# hamilton.net
KiCad netlist of a schematic drawn in EAGLE
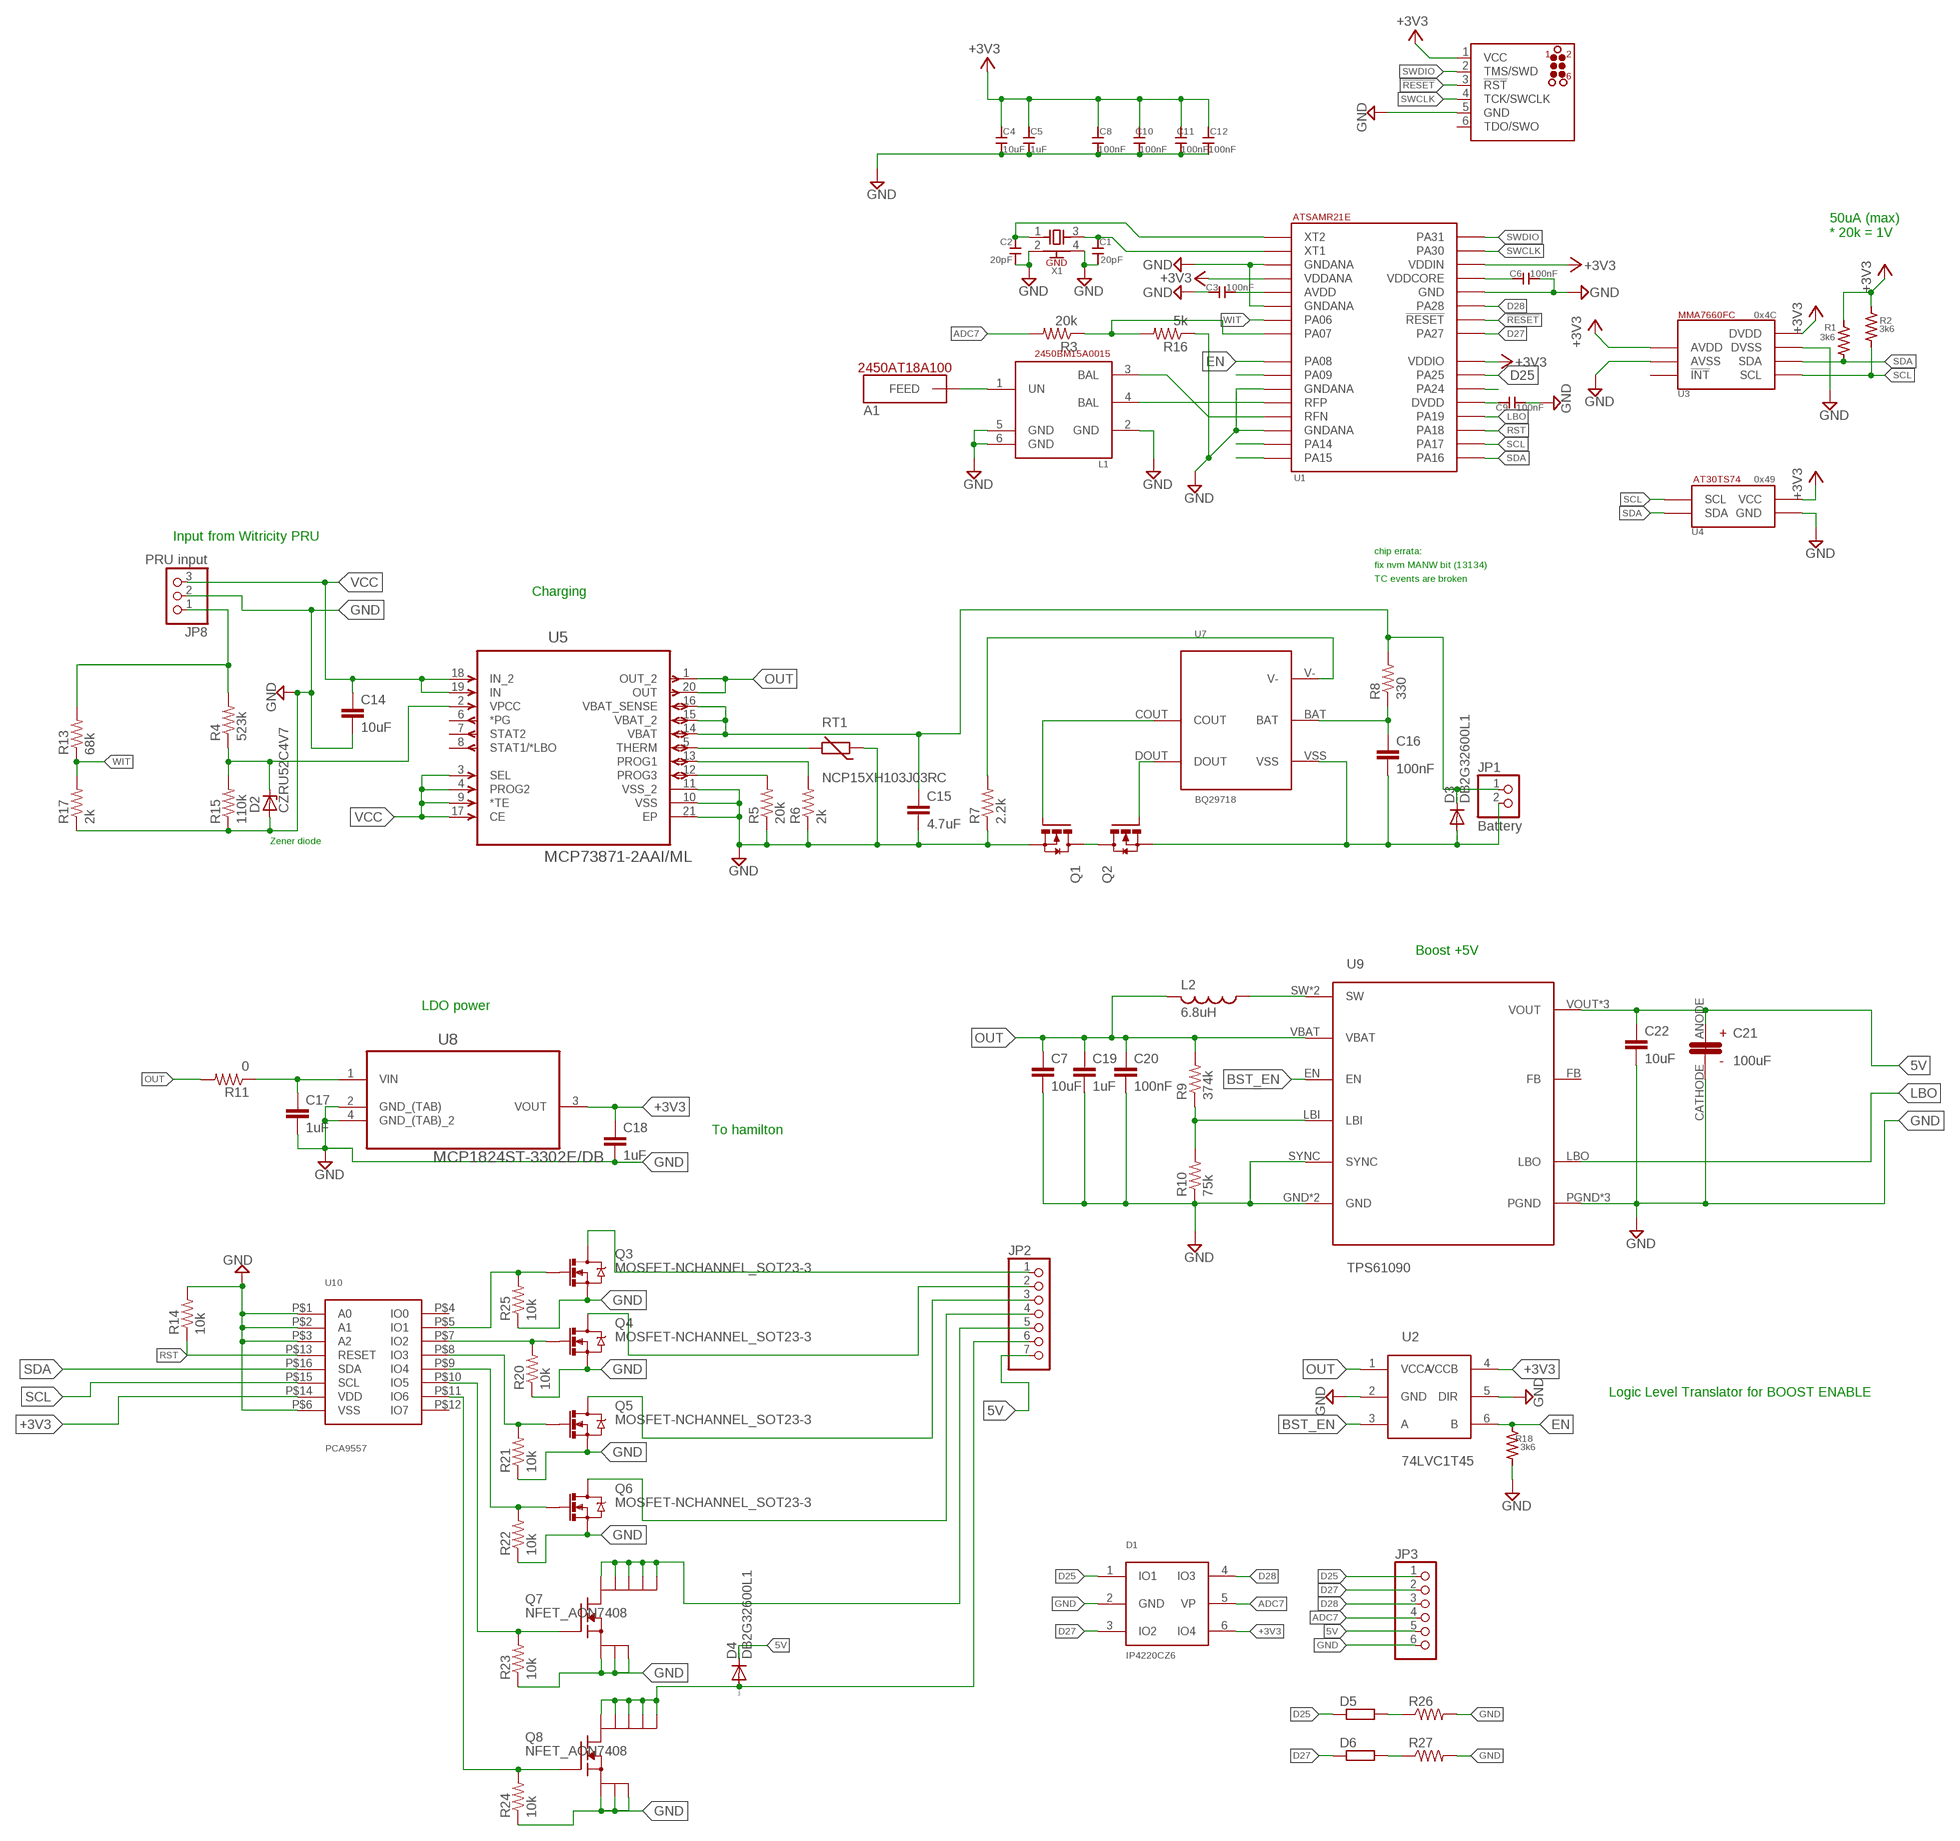
[diagram p0: schematic, sheet 1]

(export (version "E")
  (design (tool "Eeschema 10.0.6"))
  (components
    (comp (ref "A1")
      (value "JOHANSON_ANTENNA2")
      (footprint "eagle-import:JOHANSON_ANTENNA2")
      (libsource (lib "eagle-import") (part "JOHANSON_ANTENNA2"))
    )
    (comp (ref "C1")
      (value "20pF")
      (footprint "eagle-import:S0402")
      (libsource (lib "eagle-import") (part "0603_CAPACITORSMALL"))
    )
    (comp (ref "C2")
      (value "20pF")
      (footprint "eagle-import:S0402")
      (libsource (lib "eagle-import") (part "0603_CAPACITORSMALL"))
    )
    (comp (ref "C3")
      (value "100nF")
      (footprint "eagle-import:C0402")
      (libsource (lib "eagle-import") (part "0603_CAPACITOR0402"))
    )
    (comp (ref "C4")
      (value "10uF")
      (footprint "eagle-import:0805")
      (libsource (lib "eagle-import") (part "0805_CAPACITOR"))
    )
    (comp (ref "C5")
      (value "1uF")
      (footprint "eagle-import:C0402")
      (libsource (lib "eagle-import") (part "0603_CAPACITOR0402"))
    )
    (comp (ref "C6")
      (value "100nF")
      (footprint "eagle-import:C0402")
      (libsource (lib "eagle-import") (part "0603_CAPACITOR0402"))
    )
    (comp (ref "C7")
      (value "10uF")
      (footprint "eagle-import:C0603")
      (libsource (lib "eagle-import") (part "C-EUC0603"))
    )
    (comp (ref "C8")
      (value "100nF")
      (footprint "eagle-import:C0402")
      (libsource (lib "eagle-import") (part "0603_CAPACITOR0402"))
    )
    (comp (ref "C9")
      (value "100nF")
      (footprint "eagle-import:C0402")
      (libsource (lib "eagle-import") (part "0603_CAPACITOR0402"))
    )
    (comp (ref "C10")
      (value "100nF")
      (footprint "eagle-import:C0402")
      (libsource (lib "eagle-import") (part "0603_CAPACITOR0402"))
    )
    (comp (ref "C11")
      (value "100nF")
      (footprint "eagle-import:C0402")
      (libsource (lib "eagle-import") (part "0603_CAPACITOR0402"))
    )
    (comp (ref "C12")
      (value "100nF")
      (footprint "eagle-import:C0402")
      (libsource (lib "eagle-import") (part "0603_CAPACITOR0402"))
    )
    (comp (ref "C14")
      (value "10uF")
      (footprint "eagle-import:C0603")
      (libsource (lib "eagle-import") (part "C-EUC0603"))
    )
    (comp (ref "C15")
      (value "4.7uF")
      (footprint "eagle-import:C0603")
      (libsource (lib "eagle-import") (part "C-EUC0603"))
    )
    (comp (ref "C16")
      (value "100nF")
      (footprint "eagle-import:C0603")
      (libsource (lib "eagle-import") (part "C-EUC0603"))
    )
    (comp (ref "C17")
      (value "1uF")
      (footprint "eagle-import:C0603")
      (libsource (lib "eagle-import") (part "C-EUC0603"))
    )
    (comp (ref "C18")
      (value "1uF")
      (footprint "eagle-import:C0603")
      (libsource (lib "eagle-import") (part "C-EUC0603"))
    )
    (comp (ref "C19")
      (value "1uF")
      (footprint "eagle-import:C0603")
      (libsource (lib "eagle-import") (part "C-EUC0603"))
    )
    (comp (ref "C20")
      (value "100nF")
      (footprint "eagle-import:C0603")
      (libsource (lib "eagle-import") (part "C-EUC0603"))
    )
    (comp (ref "C21")
      (value "100uF")
      (footprint "eagle-import:6032")
      (libsource (lib "eagle-import") (part "T491C686K010AT"))
    )
    (comp (ref "C22")
      (value "10uF")
      (footprint "eagle-import:C0603")
      (libsource (lib "eagle-import") (part "C-EUC0603"))
    )
    (comp (ref "D1")
      (value "IP4220CZ6")
      (footprint "eagle-import:SOT457")
      (libsource (lib "eagle-import") (part "IP4220CZ6"))
    )
    (comp (ref "D2")
      (value "CZRU52C4V7")
      (footprint "eagle-import:R0603")
      (libsource (lib "eagle-import") (part "CZRU52C4V7"))
    )
    (comp (ref "D3")
      (value "DB2G32600L1")
      (footprint "eagle-import:R0402")
      (libsource (lib "eagle-import") (part "DB2G32600L1"))
    )
    (comp (ref "D4")
      (value "DB2G32600L1")
      (footprint "eagle-import:R0402")
      (libsource (lib "eagle-import") (part "DB2G32600L1"))
    )
    (comp (ref "D5")
      (value "R-EU_R0603")
      (footprint "eagle-import:R0603")
      (libsource (lib "eagle-import") (part "R-EU_R0603"))
    )
    (comp (ref "D6")
      (value "R-EU_R0603")
      (footprint "eagle-import:R0603")
      (libsource (lib "eagle-import") (part "R-EU_R0603"))
    )
    (comp (ref "JP1")
      (value "Battery")
      (footprint "eagle-import:1X02")
      (libsource (lib "eagle-import") (part "PINHD-1X2"))
    )
    (comp (ref "JP2")
      (value "PINHD-1X7")
      (footprint "eagle-import:1X07")
      (libsource (lib "eagle-import") (part "PINHD-1X7"))
    )
    (comp (ref "JP3")
      (value "PINHD-1X6")
      (footprint "eagle-import:1X06")
      (libsource (lib "eagle-import") (part "PINHD-1X6"))
    )
    (comp (ref "JP8")
      (value "PRU input")
      (footprint "eagle-import:1X03")
      (libsource (lib "eagle-import") (part "PINHD-1X3"))
    )
    (comp (ref "L1")
      (value "BALUN_JOHANSON")
      (footprint "eagle-import:BALUN_JOHANSON")
      (libsource (lib "eagle-import") (part "BALUN_JOHANSON"))
    )
    (comp (ref "L2")
      (value "6.8uH")
      (footprint "eagle-import:2-SMD-7.8-7-5")
      (libsource (lib "eagle-import") (part "L-744787068"))
    )
    (comp (ref "Q1")
      (value "CSD16301Q2")
      (footprint "eagle-import:6-SMD")
      (libsource (lib "eagle-import") (part "CSD16301Q2"))
    )
    (comp (ref "Q2")
      (value "CSD16301Q2")
      (footprint "eagle-import:6-SMD")
      (libsource (lib "eagle-import") (part "CSD16301Q2"))
    )
    (comp (ref "Q3")
      (value "MOSFET-NCHANNEL_SOT23-3")
      (footprint "eagle-import:SOT23-3")
      (libsource (lib "eagle-import") (part "MOSFET-NCHANNEL_SOT23-3"))
    )
    (comp (ref "Q4")
      (value "MOSFET-NCHANNEL_SOT23-3")
      (footprint "eagle-import:SOT23-3")
      (libsource (lib "eagle-import") (part "MOSFET-NCHANNEL_SOT23-3"))
    )
    (comp (ref "Q5")
      (value "MOSFET-NCHANNEL_SOT23-3")
      (footprint "eagle-import:SOT23-3")
      (libsource (lib "eagle-import") (part "MOSFET-NCHANNEL_SOT23-3"))
    )
    (comp (ref "Q6")
      (value "MOSFET-NCHANNEL_SOT23-3")
      (footprint "eagle-import:SOT23-3")
      (libsource (lib "eagle-import") (part "MOSFET-NCHANNEL_SOT23-3"))
    )
    (comp (ref "Q7")
      (value "NFET_AON7408")
      (footprint "eagle-import:VDFN3X38L")
      (libsource (lib "eagle-import") (part "NFET_AON7408"))
    )
    (comp (ref "Q8")
      (value "NFET_AON7408")
      (footprint "eagle-import:VDFN3X38L")
      (libsource (lib "eagle-import") (part "NFET_AON7408"))
    )
    (comp (ref "R1")
      (value "3k6")
      (footprint "eagle-import:S0402")
      (libsource (lib "eagle-import") (part "0603_RESISTORSMALL"))
    )
    (comp (ref "R2")
      (value "3k6")
      (footprint "eagle-import:S0402")
      (libsource (lib "eagle-import") (part "0603_RESISTORSMALL"))
    )
    (comp (ref "R3")
      (value "20k")
      (footprint "eagle-import:R0402")
      (libsource (lib "eagle-import") (part "R-US_R0402"))
    )
    (comp (ref "R4")
      (value "523k")
      (footprint "eagle-import:R0603")
      (libsource (lib "eagle-import") (part "R-US_R0603"))
    )
    (comp (ref "R5")
      (value "20k")
      (footprint "eagle-import:R0603")
      (libsource (lib "eagle-import") (part "R-US_R0603"))
    )
    (comp (ref "R6")
      (value "2k")
      (footprint "eagle-import:R0603")
      (libsource (lib "eagle-import") (part "R-US_R0603"))
    )
    (comp (ref "R7")
      (value "2.2k")
      (footprint "eagle-import:R0603")
      (libsource (lib "eagle-import") (part "R-US_R0603"))
    )
    (comp (ref "R8")
      (value "330")
      (footprint "eagle-import:R0603")
      (libsource (lib "eagle-import") (part "R-US_R0603"))
    )
    (comp (ref "R9")
      (value "374k")
      (footprint "eagle-import:R0603")
      (libsource (lib "eagle-import") (part "R-US_R0603"))
    )
    (comp (ref "R10")
      (value "75k")
      (footprint "eagle-import:R0603")
      (libsource (lib "eagle-import") (part "R-US_R0603"))
    )
    (comp (ref "R11")
      (value "0")
      (footprint "eagle-import:R0603")
      (libsource (lib "eagle-import") (part "R-US_R0603"))
    )
    (comp (ref "R13")
      (value "68k")
      (footprint "eagle-import:R0402")
      (libsource (lib "eagle-import") (part "R-US_R0402"))
    )
    (comp (ref "R14")
      (value "10k")
      (footprint "eagle-import:R0603")
      (libsource (lib "eagle-import") (part "R-US_R0603"))
    )
    (comp (ref "R15")
      (value "110k")
      (footprint "eagle-import:R0603")
      (libsource (lib "eagle-import") (part "R-US_R0603"))
    )
    (comp (ref "R16")
      (value "5k")
      (footprint "eagle-import:R0402")
      (libsource (lib "eagle-import") (part "R-US_R0402"))
    )
    (comp (ref "R17")
      (value "2k")
      (footprint "eagle-import:R0402")
      (libsource (lib "eagle-import") (part "R-US_R0402"))
    )
    (comp (ref "R18")
      (value "3k6")
      (footprint "eagle-import:S0402")
      (libsource (lib "eagle-import") (part "0603_RESISTORSMALL"))
    )
    (comp (ref "R20")
      (value "10k")
      (footprint "eagle-import:R0402")
      (libsource (lib "eagle-import") (part "R-US_R0402"))
    )
    (comp (ref "R21")
      (value "10k")
      (footprint "eagle-import:R0402")
      (libsource (lib "eagle-import") (part "R-US_R0402"))
    )
    (comp (ref "R22")
      (value "10k")
      (footprint "eagle-import:R0402")
      (libsource (lib "eagle-import") (part "R-US_R0402"))
    )
    (comp (ref "R23")
      (value "10k")
      (footprint "eagle-import:R0402")
      (libsource (lib "eagle-import") (part "R-US_R0402"))
    )
    (comp (ref "R24")
      (value "10k")
      (footprint "eagle-import:R0402")
      (libsource (lib "eagle-import") (part "R-US_R0402"))
    )
    (comp (ref "R25")
      (value "10k")
      (footprint "eagle-import:R0402")
      (libsource (lib "eagle-import") (part "R-US_R0402"))
    )
    (comp (ref "R26")
      (value "R-US_R0402")
      (footprint "eagle-import:R0402")
      (libsource (lib "eagle-import") (part "R-US_R0402"))
    )
    (comp (ref "R27")
      (value "R-US_R0402")
      (footprint "eagle-import:R0402")
      (libsource (lib "eagle-import") (part "R-US_R0402"))
    )
    (comp (ref "RT1")
      (value "NCP15XH103J03RC")
      (footprint "eagle-import:CT_CN0402")
      (libsource (lib "eagle-import") (part "NCP15XH103J03RC"))
    )
    (comp (ref "U$1")
      (value "JLINK_CONNECT")
      (footprint "eagle-import:TC2030-MCP-NL")
      (libsource (lib "eagle-import") (part "JLINK_CONNECT"))
    )
    (comp (ref "U1")
      (value "SAMR21")
      (footprint "eagle-import:QFN32")
      (libsource (lib "eagle-import") (part "SAMR21"))
    )
    (comp (ref "U2")
      (value "74LVC1T45")
      (footprint "eagle-import:SOT891")
      (libsource (lib "eagle-import") (part "74LVC1T45"))
    )
    (comp (ref "U3")
      (value "MMA7660FC")
      (footprint "eagle-import:MMA7660")
      (libsource (lib "eagle-import") (part "MMA7660FC"))
    )
    (comp (ref "U4")
      (value "AT30TS74")
      (footprint "eagle-import:4WLCSP")
      (libsource (lib "eagle-import") (part "AT30TS74"))
    )
    (comp (ref "U5")
      (value "MCP73871-2AAI/ML")
      (footprint "eagle-import:QFN50P400X400X100-21N")
      (libsource (lib "eagle-import") (part "MCP73871-2AAI/ML"))
    )
    (comp (ref "U7")
      (value "BQ29718")
      (footprint "eagle-import:6-WFDFN")
      (libsource (lib "eagle-import") (part "BQ29718"))
    )
    (comp (ref "U8")
      (value "MCP1824ST-3302E/DB")
      (footprint "eagle-import:SOT230P700X180-4N")
      (libsource (lib "eagle-import") (part "MCP1824ST-3302E/DB"))
    )
    (comp (ref "U9")
      (value "TPS61090")
      (footprint "eagle-import:QFN-16")
      (libsource (lib "eagle-import") (part "TPS61090"))
    )
    (comp (ref "U10")
      (value "PCA9557")
      (footprint "eagle-import:SOT629-1")
      (libsource (lib "eagle-import") (part "PCA9557"))
    )
    (comp (ref "X1")
      (value "XTAL")
      (footprint "eagle-import:XTAL")
      (libsource (lib "eagle-import") (part "XTAL"))
    )
  )
  (nets
    (net (code "1") (name "+3V3") (class "Default")
      (node (ref "C10") (pin "1") (pinfunction "P$1_1") (pintype "passive"))
      (node (ref "C11") (pin "1") (pinfunction "P$1_1") (pintype "passive"))
      (node (ref "C12") (pin "1") (pinfunction "P$1_1") (pintype "passive"))
      (node (ref "C18") (pin "1") (pinfunction "1_1") (pintype "passive"))
      (node (ref "C4") (pin "2") (pinfunction "P$2_2") (pintype "passive"))
      (node (ref "C5") (pin "2") (pinfunction "P$2_2") (pintype "passive"))
      (node (ref "C8") (pin "1") (pinfunction "P$1_1") (pintype "passive"))
      (node (ref "D1") (pin "6") (pinfunction "IO4_6") (pintype "bidirectional"))
      (node (ref "R1") (pin "P$2") (pinfunction "P$2_P$2") (pintype "passive"))
      (node (ref "R2") (pin "P$2") (pinfunction "P$2_P$2") (pintype "passive"))
      (node (ref "U$1") (pin "1") (pinfunction "VCC_1") (pintype "passive"))
      (node (ref "U1") (pin "24") (pinfunction "VDDIO_24") (pintype "bidirectional"))
      (node (ref "U1") (pin "30") (pinfunction "VDDIN_30") (pintype "bidirectional"))
      (node (ref "U1") (pin "4") (pinfunction "VDDANA_4") (pintype "bidirectional"))
      (node (ref "U10") (pin "P$14") (pinfunction "VDD_P$14") (pintype "bidirectional"))
      (node (ref "U2") (pin "4") (pinfunction "VCCB_4") (pintype "bidirectional"))
      (node (ref "U3") (pin "3") (pinfunction "AVDD_3") (pintype "bidirectional"))
      (node (ref "U3") (pin "9") (pinfunction "DVDD_9") (pintype "bidirectional"))
      (node (ref "U4") (pin "A1") (pinfunction "VCC_A1") (pintype "bidirectional"))
      (node (ref "U8") (pin "3") (pinfunction "VOUT_3") (pintype "output"))
    )
    (net (code "2") (name "/~{RESET}") (class "Default")
      (node (ref "U$1") (pin "3") (pinfunction "~{RST}_3") (pintype "bidirectional"))
      (node (ref "U1") (pin "26") (pinfunction "~{RESET}_26") (pintype "bidirectional"))
    )
    (net (code "3") (name "5V") (class "Default")
      (node (ref "C21") (pin "ANODE") (pinfunction "ANODE_ANODE") (pintype "bidirectional"))
      (node (ref "C22") (pin "1") (pinfunction "1_1") (pintype "passive"))
      (node (ref "D4") (pin "C") (pinfunction "C_C") (pintype "passive"))
      (node (ref "JP2") (pin "7") (pinfunction "7_7") (pintype "passive"))
      (node (ref "JP3") (pin "5") (pinfunction "5_5") (pintype "passive"))
      (node (ref "U9") (pin "VOUT") (pinfunction "VOUT_VOUT") (pintype "bidirectional"))
      (node (ref "U9") (pin "VOUT_2") (pinfunction "VOUT_VOUT_2") (pintype "bidirectional"))
      (node (ref "U9") (pin "VOUT_3") (pinfunction "VOUT_VOUT_3") (pintype "bidirectional"))
    )
    (net (code "4") (name "ADC7") (class "Default")
      (node (ref "D1") (pin "5") (pinfunction "VP_5") (pintype "bidirectional"))
      (node (ref "JP3") (pin "4") (pinfunction "4_4") (pintype "passive"))
      (node (ref "R3") (pin "2") (pinfunction "2_2") (pintype "passive"))
    )
    (net (code "5") (name "BST_EN") (class "Default")
      (node (ref "U2") (pin "3") (pinfunction "A_3") (pintype "bidirectional"))
      (node (ref "U9") (pin "EN") (pinfunction "EN_EN") (pintype "bidirectional"))
    )
    (net (code "6") (name "D25") (class "Default")
      (node (ref "D1") (pin "1") (pinfunction "IO1_1") (pintype "bidirectional"))
      (node (ref "D5") (pin "1") (pinfunction "1_1") (pintype "passive"))
      (node (ref "JP3") (pin "1") (pinfunction "1_1") (pintype "passive"))
      (node (ref "U1") (pin "23") (pinfunction "PA25_23") (pintype "bidirectional"))
    )
    (net (code "7") (name "D27") (class "Default")
      (node (ref "D1") (pin "3") (pinfunction "IO2_3") (pintype "bidirectional"))
      (node (ref "D6") (pin "1") (pinfunction "1_1") (pintype "passive"))
      (node (ref "JP3") (pin "2") (pinfunction "2_2") (pintype "passive"))
      (node (ref "U1") (pin "25") (pinfunction "PA27_25") (pintype "bidirectional"))
    )
    (net (code "8") (name "D28") (class "Default")
      (node (ref "D1") (pin "4") (pinfunction "IO3_4") (pintype "bidirectional"))
      (node (ref "JP3") (pin "3") (pinfunction "3_3") (pintype "passive"))
      (node (ref "U1") (pin "27") (pinfunction "PA28_27") (pintype "bidirectional"))
    )
    (net (code "9") (name "EN") (class "Default")
      (node (ref "R18") (pin "P$2") (pinfunction "P$2_P$2") (pintype "passive"))
      (node (ref "U1") (pin "9") (pinfunction "PA08_9") (pintype "bidirectional"))
      (node (ref "U2") (pin "6") (pinfunction "B_6") (pintype "bidirectional"))
    )
    (net (code "10") (name "GND") (class "Default")
      (node (ref "C1") (pin "P$1") (pinfunction "P$1_P$1") (pintype "passive"))
      (node (ref "C10") (pin "2") (pinfunction "P$2_2") (pintype "passive"))
      (node (ref "C11") (pin "2") (pinfunction "P$2_2") (pintype "passive"))
      (node (ref "C12") (pin "2") (pinfunction "P$2_2") (pintype "passive"))
      (node (ref "C14") (pin "2") (pinfunction "2_2") (pintype "passive"))
      (node (ref "C15") (pin "2") (pinfunction "2_2") (pintype "passive"))
      (node (ref "C17") (pin "2") (pinfunction "2_2") (pintype "passive"))
      (node (ref "C18") (pin "2") (pinfunction "2_2") (pintype "passive"))
      (node (ref "C19") (pin "2") (pinfunction "2_2") (pintype "passive"))
      (node (ref "C2") (pin "P$1") (pinfunction "P$1_P$1") (pintype "passive"))
      (node (ref "C20") (pin "2") (pinfunction "2_2") (pintype "passive"))
      (node (ref "C21") (pin "CATHODE") (pinfunction "CATHODE_CATHODE") (pintype "bidirectional"))
      (node (ref "C22") (pin "2") (pinfunction "2_2") (pintype "passive"))
      (node (ref "C3") (pin "2") (pinfunction "P$2_2") (pintype "passive"))
      (node (ref "C4") (pin "1") (pinfunction "P$1_1") (pintype "passive"))
      (node (ref "C5") (pin "1") (pinfunction "P$1_1") (pintype "passive"))
      (node (ref "C6") (pin "1") (pinfunction "P$1_1") (pintype "passive"))
      (node (ref "C7") (pin "2") (pinfunction "2_2") (pintype "passive"))
      (node (ref "C8") (pin "2") (pinfunction "P$2_2") (pintype "passive"))
      (node (ref "C9") (pin "1") (pinfunction "P$1_1") (pintype "passive"))
      (node (ref "D1") (pin "2") (pinfunction "GND_2") (pintype "bidirectional"))
      (node (ref "D2") (pin "A") (pinfunction "A_A") (pintype "passive"))
      (node (ref "JP3") (pin "6") (pinfunction "6_6") (pintype "passive"))
      (node (ref "JP8") (pin "2") (pinfunction "2_2") (pintype "passive"))
      (node (ref "L1") (pin "2") (pinfunction "GND_2") (pintype "bidirectional"))
      (node (ref "L1") (pin "5") (pinfunction "GND_5") (pintype "bidirectional"))
      (node (ref "L1") (pin "6") (pinfunction "GND_6") (pintype "bidirectional"))
      (node (ref "Q1") (pin "S_1") (pinfunction "S_S_1") (pintype "passive"))
      (node (ref "Q1") (pin "S_2") (pinfunction "S_S_2") (pintype "passive"))
      (node (ref "Q3") (pin "2") (pinfunction "S_2") (pintype "passive"))
      (node (ref "Q4") (pin "2") (pinfunction "S_2") (pintype "passive"))
      (node (ref "Q5") (pin "2") (pinfunction "S_2") (pintype "passive"))
      (node (ref "Q6") (pin "2") (pinfunction "S_2") (pintype "passive"))
      (node (ref "Q7") (pin "1") (pinfunction "S_1") (pintype "passive"))
      (node (ref "Q7") (pin "2") (pinfunction "S_2") (pintype "bidirectional"))
      (node (ref "Q7") (pin "3") (pinfunction "S_3") (pintype "bidirectional"))
      (node (ref "Q8") (pin "1") (pinfunction "S_1") (pintype "passive"))
      (node (ref "Q8") (pin "2") (pinfunction "S_2") (pintype "bidirectional"))
      (node (ref "Q8") (pin "3") (pinfunction "S_3") (pintype "bidirectional"))
      (node (ref "R10") (pin "1") (pinfunction "1_1") (pintype "passive"))
      (node (ref "R14") (pin "2") (pinfunction "2_2") (pintype "passive"))
      (node (ref "R15") (pin "1") (pinfunction "1_1") (pintype "passive"))
      (node (ref "R16") (pin "1") (pinfunction "1_1") (pintype "passive"))
      (node (ref "R17") (pin "1") (pinfunction "1_1") (pintype "passive"))
      (node (ref "R18") (pin "P$1") (pinfunction "P$1_P$1") (pintype "passive"))
      (node (ref "R20") (pin "1") (pinfunction "1_1") (pintype "passive"))
      (node (ref "R21") (pin "1") (pinfunction "1_1") (pintype "passive"))
      (node (ref "R22") (pin "1") (pinfunction "1_1") (pintype "passive"))
      (node (ref "R23") (pin "1") (pinfunction "1_1") (pintype "passive"))
      (node (ref "R24") (pin "1") (pinfunction "1_1") (pintype "passive"))
      (node (ref "R25") (pin "1") (pinfunction "1_1") (pintype "passive"))
      (node (ref "R26") (pin "2") (pinfunction "2_2") (pintype "passive"))
      (node (ref "R27") (pin "2") (pinfunction "2_2") (pintype "passive"))
      (node (ref "R5") (pin "1") (pinfunction "1_1") (pintype "passive"))
      (node (ref "R6") (pin "1") (pinfunction "1_1") (pintype "passive"))
      (node (ref "R7") (pin "1") (pinfunction "1_1") (pintype "passive"))
      (node (ref "RT1") (pin "1") (pinfunction "1_1") (pintype "passive"))
      (node (ref "U$1") (pin "5") (pinfunction "GND_5") (pintype "power_in"))
      (node (ref "U1") (pin "11") (pinfunction "GNDANA_11") (pintype "bidirectional"))
      (node (ref "U1") (pin "14") (pinfunction "GNDANA_14") (pintype "bidirectional"))
      (node (ref "U1") (pin "28") (pinfunction "GND_28") (pintype "bidirectional"))
      (node (ref "U1") (pin "3") (pinfunction "GNDANA_3") (pintype "bidirectional"))
      (node (ref "U1") (pin "6") (pinfunction "GNDANA_6") (pintype "bidirectional"))
      (node (ref "U10") (pin "P$1") (pinfunction "A0_P$1") (pintype "bidirectional"))
      (node (ref "U10") (pin "P$2") (pinfunction "A1_P$2") (pintype "bidirectional"))
      (node (ref "U10") (pin "P$3") (pinfunction "A2_P$3") (pintype "bidirectional"))
      (node (ref "U10") (pin "P$6") (pinfunction "VSS_P$6") (pintype "bidirectional"))
      (node (ref "U2") (pin "2") (pinfunction "GND_2") (pintype "bidirectional"))
      (node (ref "U2") (pin "5") (pinfunction "DIR_5") (pintype "bidirectional"))
      (node (ref "U3") (pin "4") (pinfunction "AVSS_4") (pintype "bidirectional"))
      (node (ref "U3") (pin "8") (pinfunction "DVSS_8") (pintype "bidirectional"))
      (node (ref "U4") (pin "A2") (pinfunction "GND_A2") (pintype "bidirectional"))
      (node (ref "U5") (pin "10") (pinfunction "VSS_10") (pintype "power_in"))
      (node (ref "U5") (pin "11") (pinfunction "VSS_2_11") (pintype "power_in"))
      (node (ref "U5") (pin "21") (pinfunction "EP_21") (pintype "passive"))
      (node (ref "U8") (pin "2") (pinfunction "GND_(TAB)_2") (pintype "passive"))
      (node (ref "U8") (pin "4") (pinfunction "GND_(TAB)_2_4") (pintype "passive"))
      (node (ref "U9") (pin "GND") (pinfunction "GND_GND") (pintype "bidirectional"))
      (node (ref "U9") (pin "P$17") (pinfunction "GND_P$17") (pintype "bidirectional"))
      (node (ref "U9") (pin "PGND") (pinfunction "PGND_PGND") (pintype "bidirectional"))
      (node (ref "U9") (pin "PGND_2") (pinfunction "PGND_PGND_2") (pintype "bidirectional"))
      (node (ref "U9") (pin "PGND_3") (pinfunction "PGND_PGND_3") (pintype "bidirectional"))
      (node (ref "U9") (pin "SYNC") (pinfunction "SYNC_SYNC") (pintype "bidirectional"))
      (node (ref "X1") (pin "2") (pinfunction "GND_2") (pintype "power_in"))
      (node (ref "X1") (pin "4") (pinfunction "GND_4") (pintype "power_in"))
    )
    (net (code "11") (name "LBO") (class "Default")
      (node (ref "U1") (pin "20") (pinfunction "PA19_20") (pintype "bidirectional"))
      (node (ref "U9") (pin "LBO") (pinfunction "LBO_LBO") (pintype "bidirectional"))
    )
    (net (code "12") (name "Net-(C3-P$1)") (class "Default")
      (node (ref "C3") (pin "1") (pinfunction "P$1_1") (pintype "passive"))
      (node (ref "U1") (pin "5") (pinfunction "AVDD_5") (pintype "bidirectional"))
    )
    (net (code "13") (name "Net-(C6-P$2)") (class "Default")
      (node (ref "C6") (pin "2") (pinfunction "P$2_2") (pintype "passive"))
      (node (ref "U1") (pin "29") (pinfunction "VDDCORE_29") (pintype "bidirectional"))
    )
    (net (code "14") (name "Net-(C9-P$2)") (class "Default")
      (node (ref "C9") (pin "2") (pinfunction "P$2_2") (pintype "passive"))
      (node (ref "U1") (pin "21") (pinfunction "DVDD_21") (pintype "bidirectional"))
    )
    (net (code "15") (name "Net-(C16-Pad1)") (class "Default")
      (node (ref "C16") (pin "1") (pinfunction "1_1") (pintype "passive"))
      (node (ref "R8") (pin "1") (pinfunction "1_1") (pintype "passive"))
      (node (ref "U7") (pin "BAT") (pinfunction "BAT_BAT") (pintype "bidirectional"))
    )
    (net (code "16") (name "Net-(C16-Pad2)") (class "Default")
      (node (ref "C16") (pin "2") (pinfunction "2_2") (pintype "passive"))
      (node (ref "D3") (pin "A") (pinfunction "A_A") (pintype "passive"))
      (node (ref "JP1") (pin "2") (pinfunction "2_2") (pintype "passive"))
      (node (ref "Q2") (pin "S_1") (pinfunction "S_S_1") (pintype "passive"))
      (node (ref "Q2") (pin "S_2") (pinfunction "S_S_2") (pintype "passive"))
      (node (ref "U7") (pin "VSS") (pinfunction "VSS_VSS") (pintype "bidirectional"))
    )
    (net (code "17") (name "Net-(D4-PadA)") (class "Default")
      (node (ref "D4") (pin "A") (pinfunction "A_A") (pintype "passive"))
      (node (ref "JP2") (pin "6") (pinfunction "6_6") (pintype "passive"))
      (node (ref "Q8") (pin "5") (pinfunction "D_5") (pintype "bidirectional"))
      (node (ref "Q8") (pin "6") (pinfunction "D_6") (pintype "bidirectional"))
      (node (ref "Q8") (pin "7") (pinfunction "D_7") (pintype "bidirectional"))
      (node (ref "Q8") (pin "8") (pinfunction "D_8") (pintype "passive"))
      (node (ref "Q8") (pin "PAD") (pinfunction "D_PAD") (pintype "bidirectional"))
    )
    (net (code "18") (name "Net-(D5-Pad2)") (class "Default")
      (node (ref "D5") (pin "2") (pinfunction "2_2") (pintype "passive"))
      (node (ref "R26") (pin "1") (pinfunction "1_1") (pintype "passive"))
    )
    (net (code "19") (name "Net-(D6-Pad2)") (class "Default")
      (node (ref "D6") (pin "2") (pinfunction "2_2") (pintype "passive"))
      (node (ref "R27") (pin "1") (pinfunction "1_1") (pintype "passive"))
    )
    (net (code "20") (name "Net-(JP2-Pad5)") (class "Default")
      (node (ref "JP2") (pin "5") (pinfunction "5_5") (pintype "passive"))
      (node (ref "Q7") (pin "5") (pinfunction "D_5") (pintype "bidirectional"))
      (node (ref "Q7") (pin "6") (pinfunction "D_6") (pintype "bidirectional"))
      (node (ref "Q7") (pin "7") (pinfunction "D_7") (pintype "bidirectional"))
      (node (ref "Q7") (pin "8") (pinfunction "D_8") (pintype "passive"))
      (node (ref "Q7") (pin "PAD") (pinfunction "D_PAD") (pintype "bidirectional"))
    )
    (net (code "21") (name "Net-(JP8-Pad1)") (class "Default")
      (node (ref "JP8") (pin "1") (pinfunction "1_1") (pintype "passive"))
      (node (ref "R13") (pin "2") (pinfunction "2_2") (pintype "passive"))
      (node (ref "R4") (pin "2") (pinfunction "2_2") (pintype "passive"))
    )
    (net (code "22") (name "Net-(L1-UN)") (class "Default")
      (node (ref "A1") (pin "FEED") (pinfunction "FEED_FEED") (pintype "bidirectional"))
      (node (ref "L1") (pin "1") (pinfunction "UN_1") (pintype "bidirectional"))
    )
    (net (code "23") (name "Net-(L2-1)") (class "Default")
      (node (ref "L2") (pin "P$1") (pinfunction "1_P$1") (pintype "passive"))
      (node (ref "U9") (pin "SW") (pinfunction "SW_SW") (pintype "bidirectional"))
      (node (ref "U9") (pin "SW_2") (pinfunction "SW_SW_2") (pintype "bidirectional"))
    )
    (net (code "24") (name "Net-(Q1-D-PadD_1)") (class "Default")
      (node (ref "Q1") (pin "D_1") (pinfunction "D_D_1") (pintype "passive"))
      (node (ref "Q1") (pin "D_2") (pinfunction "D_D_2") (pintype "passive"))
      (node (ref "Q1") (pin "D_3") (pinfunction "D_D_3") (pintype "passive"))
      (node (ref "Q1") (pin "D_4") (pinfunction "D_D_4") (pintype "passive"))
      (node (ref "Q1") (pin "D_5") (pinfunction "D_D_5") (pintype "passive"))
      (node (ref "Q2") (pin "D_1") (pinfunction "D_D_1") (pintype "passive"))
      (node (ref "Q2") (pin "D_2") (pinfunction "D_D_2") (pintype "passive"))
      (node (ref "Q2") (pin "D_3") (pinfunction "D_D_3") (pintype "passive"))
      (node (ref "Q2") (pin "D_4") (pinfunction "D_D_4") (pintype "passive"))
      (node (ref "Q2") (pin "D_5") (pinfunction "D_D_5") (pintype "passive"))
    )
    (net (code "25") (name "Net-(Q1-PadG)") (class "Default")
      (node (ref "Q1") (pin "G") (pinfunction "G_G") (pintype "passive"))
      (node (ref "U7") (pin "COUT") (pinfunction "COUT_COUT") (pintype "bidirectional"))
    )
    (net (code "26") (name "Net-(Q2-PadG)") (class "Default")
      (node (ref "Q2") (pin "G") (pinfunction "G_G") (pintype "passive"))
      (node (ref "U7") (pin "DOUT") (pinfunction "DOUT_DOUT") (pintype "bidirectional"))
    )
    (net (code "27") (name "Net-(Q3-D)") (class "Default")
      (node (ref "JP2") (pin "1") (pinfunction "1_1") (pintype "passive"))
      (node (ref "Q3") (pin "3") (pinfunction "D_3") (pintype "passive"))
    )
    (net (code "28") (name "Net-(Q3-G)") (class "Default")
      (node (ref "Q3") (pin "1") (pinfunction "G_1") (pintype "passive"))
      (node (ref "R25") (pin "2") (pinfunction "2_2") (pintype "passive"))
      (node (ref "U10") (pin "P$5") (pinfunction "IO1_P$5") (pintype "bidirectional"))
    )
    (net (code "29") (name "Net-(Q4-D)") (class "Default")
      (node (ref "JP2") (pin "2") (pinfunction "2_2") (pintype "passive"))
      (node (ref "Q4") (pin "3") (pinfunction "D_3") (pintype "passive"))
    )
    (net (code "30") (name "Net-(Q4-G)") (class "Default")
      (node (ref "Q4") (pin "1") (pinfunction "G_1") (pintype "passive"))
      (node (ref "R20") (pin "2") (pinfunction "2_2") (pintype "passive"))
      (node (ref "U10") (pin "P$7") (pinfunction "IO2_P$7") (pintype "bidirectional"))
    )
    (net (code "31") (name "Net-(Q5-D)") (class "Default")
      (node (ref "JP2") (pin "3") (pinfunction "3_3") (pintype "passive"))
      (node (ref "Q5") (pin "3") (pinfunction "D_3") (pintype "passive"))
    )
    (net (code "32") (name "Net-(Q5-G)") (class "Default")
      (node (ref "Q5") (pin "1") (pinfunction "G_1") (pintype "passive"))
      (node (ref "R21") (pin "2") (pinfunction "2_2") (pintype "passive"))
      (node (ref "U10") (pin "P$8") (pinfunction "IO3_P$8") (pintype "bidirectional"))
    )
    (net (code "33") (name "Net-(Q6-D)") (class "Default")
      (node (ref "JP2") (pin "4") (pinfunction "4_4") (pintype "passive"))
      (node (ref "Q6") (pin "3") (pinfunction "D_3") (pintype "passive"))
    )
    (net (code "34") (name "Net-(Q6-G)") (class "Default")
      (node (ref "Q6") (pin "1") (pinfunction "G_1") (pintype "passive"))
      (node (ref "R22") (pin "2") (pinfunction "2_2") (pintype "passive"))
      (node (ref "U10") (pin "P$9") (pinfunction "IO4_P$9") (pintype "bidirectional"))
    )
    (net (code "35") (name "Net-(Q7-G)") (class "Default")
      (node (ref "Q7") (pin "4") (pinfunction "G_4") (pintype "passive"))
      (node (ref "R23") (pin "2") (pinfunction "2_2") (pintype "passive"))
      (node (ref "U10") (pin "P$10") (pinfunction "IO5_P$10") (pintype "bidirectional"))
    )
    (net (code "36") (name "Net-(Q8-G)") (class "Default")
      (node (ref "Q8") (pin "4") (pinfunction "G_4") (pintype "passive"))
      (node (ref "R24") (pin "2") (pinfunction "2_2") (pintype "passive"))
      (node (ref "U10") (pin "P$11") (pinfunction "IO6_P$11") (pintype "bidirectional"))
    )
    (net (code "37") (name "Net-(R7-Pad2)") (class "Default")
      (node (ref "R7") (pin "2") (pinfunction "2_2") (pintype "passive"))
      (node (ref "U7") (pin "V-") (pinfunction "V-_V-") (pintype "bidirectional"))
    )
    (net (code "38") (name "Net-(R10-Pad2)") (class "Default")
      (node (ref "R10") (pin "2") (pinfunction "2_2") (pintype "passive"))
      (node (ref "R9") (pin "1") (pinfunction "1_1") (pintype "passive"))
      (node (ref "U9") (pin "LBI") (pinfunction "LBI_LBI") (pintype "bidirectional"))
    )
    (net (code "39") (name "Net-(U1-PA07)") (class "Default")
      (node (ref "R16") (pin "2") (pinfunction "2_2") (pintype "passive"))
      (node (ref "R3") (pin "1") (pinfunction "1_1") (pintype "passive"))
      (node (ref "U1") (pin "8") (pinfunction "PA07_8") (pintype "bidirectional"))
    )
    (net (code "40") (name "Net-(U1-RFN)") (class "Default")
      (node (ref "L1") (pin "3") (pinfunction "BAL_3") (pintype "bidirectional"))
      (node (ref "U1") (pin "13") (pinfunction "RFN_13") (pintype "bidirectional"))
    )
    (net (code "41") (name "Net-(U1-RFP)") (class "Default")
      (node (ref "L1") (pin "4") (pinfunction "BAL_4") (pintype "bidirectional"))
      (node (ref "U1") (pin "12") (pinfunction "RFP_12") (pintype "bidirectional"))
    )
    (net (code "42") (name "Net-(U1-XT1)") (class "Default")
      (node (ref "C1") (pin "P$2") (pinfunction "P$2_P$2") (pintype "passive"))
      (node (ref "U1") (pin "2") (pinfunction "XT1_2") (pintype "bidirectional"))
      (node (ref "X1") (pin "3") (pinfunction "X2_3") (pintype "power_in"))
    )
    (net (code "43") (name "Net-(U1-XT2)") (class "Default")
      (node (ref "C2") (pin "P$2") (pinfunction "P$2_P$2") (pintype "passive"))
      (node (ref "U1") (pin "1") (pinfunction "XT2_1") (pintype "bidirectional"))
      (node (ref "X1") (pin "1") (pinfunction "X1_1") (pintype "power_in"))
    )
    (net (code "44") (name "Net-(U5-PROG1)") (class "Default")
      (node (ref "R6") (pin "2") (pinfunction "2_2") (pintype "passive"))
      (node (ref "U5") (pin "13") (pinfunction "PROG1_13") (pintype "bidirectional"))
    )
    (net (code "45") (name "Net-(U5-PROG3)") (class "Default")
      (node (ref "R5") (pin "2") (pinfunction "2_2") (pintype "passive"))
      (node (ref "U5") (pin "12") (pinfunction "PROG3_12") (pintype "bidirectional"))
    )
    (net (code "46") (name "Net-(U5-THERM)") (class "Default")
      (node (ref "RT1") (pin "2") (pinfunction "2_2") (pintype "passive"))
      (node (ref "U5") (pin "5") (pinfunction "THERM_5") (pintype "bidirectional"))
    )
    (net (code "47") (name "Net-(U5-VBAT)") (class "Default")
      (node (ref "C15") (pin "1") (pinfunction "1_1") (pintype "passive"))
      (node (ref "D3") (pin "C") (pinfunction "C_C") (pintype "passive"))
      (node (ref "JP1") (pin "1") (pinfunction "1_1") (pintype "passive"))
      (node (ref "R8") (pin "2") (pinfunction "2_2") (pintype "passive"))
      (node (ref "U5") (pin "14") (pinfunction "VBAT_14") (pintype "bidirectional"))
      (node (ref "U5") (pin "15") (pinfunction "VBAT_2_15") (pintype "bidirectional"))
      (node (ref "U5") (pin "16") (pinfunction "VBAT_SENSE_16") (pintype "bidirectional"))
    )
    (net (code "48") (name "Net-(U5-VPCC)") (class "Default")
      (node (ref "D2") (pin "C") (pinfunction "C_C") (pintype "passive"))
      (node (ref "R15") (pin "2") (pinfunction "2_2") (pintype "passive"))
      (node (ref "R4") (pin "1") (pinfunction "1_1") (pintype "passive"))
      (node (ref "U5") (pin "2") (pinfunction "VPCC_2") (pintype "input"))
    )
    (net (code "49") (name "Net-(U8-VIN)") (class "Default")
      (node (ref "C17") (pin "1") (pinfunction "1_1") (pintype "passive"))
      (node (ref "R11") (pin "1") (pinfunction "1_1") (pintype "passive"))
      (node (ref "U8") (pin "1") (pinfunction "VIN_1") (pintype "input"))
    )
    (net (code "50") (name "OUT") (class "Default")
      (node (ref "C19") (pin "1") (pinfunction "1_1") (pintype "passive"))
      (node (ref "C20") (pin "1") (pinfunction "1_1") (pintype "passive"))
      (node (ref "C7") (pin "1") (pinfunction "1_1") (pintype "passive"))
      (node (ref "L2") (pin "P$2") (pinfunction "2_P$2") (pintype "passive"))
      (node (ref "R11") (pin "2") (pinfunction "2_2") (pintype "passive"))
      (node (ref "R9") (pin "2") (pinfunction "2_2") (pintype "passive"))
      (node (ref "U2") (pin "1") (pinfunction "VCCA_1") (pintype "bidirectional"))
      (node (ref "U5") (pin "1") (pinfunction "OUT_2_1") (pintype "output"))
      (node (ref "U5") (pin "20") (pinfunction "OUT_20") (pintype "output"))
      (node (ref "U9") (pin "VBAT") (pinfunction "VBAT_VBAT") (pintype "bidirectional"))
    )
    (net (code "51") (name "RST") (class "Default")
      (node (ref "R14") (pin "1") (pinfunction "1_1") (pintype "passive"))
      (node (ref "U1") (pin "19") (pinfunction "PA18_19") (pintype "bidirectional"))
      (node (ref "U10") (pin "P$13") (pinfunction "RESET_P$13") (pintype "bidirectional"))
    )
    (net (code "52") (name "SCL") (class "Default")
      (node (ref "R2") (pin "P$1") (pinfunction "P$1_P$1") (pintype "passive"))
      (node (ref "U1") (pin "18") (pinfunction "PA17_18") (pintype "bidirectional"))
      (node (ref "U10") (pin "P$15") (pinfunction "SCL_P$15") (pintype "bidirectional"))
      (node (ref "U3") (pin "6") (pinfunction "SCL_6") (pintype "bidirectional"))
      (node (ref "U4") (pin "B2") (pinfunction "SCL_B2") (pintype "bidirectional"))
    )
    (net (code "53") (name "SDA") (class "Default")
      (node (ref "R1") (pin "P$1") (pinfunction "P$1_P$1") (pintype "passive"))
      (node (ref "U1") (pin "17") (pinfunction "PA16_17") (pintype "bidirectional"))
      (node (ref "U10") (pin "P$16") (pinfunction "SDA_P$16") (pintype "bidirectional"))
      (node (ref "U3") (pin "7") (pinfunction "SDA_7") (pintype "bidirectional"))
      (node (ref "U4") (pin "B1") (pinfunction "SDA_B1") (pintype "bidirectional"))
    )
    (net (code "54") (name "SWCLK") (class "Default")
      (node (ref "U$1") (pin "4") (pinfunction "TCK/SWCLK_4") (pintype "bidirectional"))
      (node (ref "U1") (pin "31") (pinfunction "PA30_31") (pintype "bidirectional"))
    )
    (net (code "55") (name "SWDIO") (class "Default")
      (node (ref "U$1") (pin "2") (pinfunction "TMS/SWD_2") (pintype "bidirectional"))
      (node (ref "U1") (pin "32") (pinfunction "PA31_32") (pintype "bidirectional"))
    )
    (net (code "56") (name "VCC") (class "Default")
      (node (ref "C14") (pin "1") (pinfunction "1_1") (pintype "passive"))
      (node (ref "JP8") (pin "3") (pinfunction "3_3") (pintype "passive"))
      (node (ref "U5") (pin "17") (pinfunction "CE_17") (pintype "input"))
      (node (ref "U5") (pin "18") (pinfunction "IN_2_18") (pintype "input"))
      (node (ref "U5") (pin "19") (pinfunction "IN_19") (pintype "input"))
      (node (ref "U5") (pin "3") (pinfunction "SEL_3") (pintype "input"))
      (node (ref "U5") (pin "4") (pinfunction "PROG2_4") (pintype "input"))
      (node (ref "U5") (pin "9") (pinfunction "*TE_9") (pintype "input"))
    )
    (net (code "57") (name "WIT") (class "Default")
      (node (ref "R13") (pin "1") (pinfunction "1_1") (pintype "passive"))
      (node (ref "R17") (pin "2") (pinfunction "2_2") (pintype "passive"))
      (node (ref "U1") (pin "7") (pinfunction "PA06_7") (pintype "bidirectional"))
    )
    (net (code "58") (name "unconnected-(U$1-TDO{slash}SWO-Pad6)") (class "Default")
      (node (ref "U$1") (pin "6") (pinfunction "TDO/SWO_6") (pintype "bidirectional"))
    )
    (net (code "59") (name "unconnected-(U1-PA09-Pad10)") (class "Default")
      (node (ref "U1") (pin "10") (pinfunction "PA09_10") (pintype "bidirectional"))
    )
    (net (code "60") (name "unconnected-(U1-PA14-Pad15)") (class "Default")
      (node (ref "U1") (pin "15") (pinfunction "PA14_15") (pintype "bidirectional"))
    )
    (net (code "61") (name "unconnected-(U1-PA15-Pad16)") (class "Default")
      (node (ref "U1") (pin "16") (pinfunction "PA15_16") (pintype "bidirectional"))
    )
    (net (code "62") (name "unconnected-(U1-PA24-Pad22)") (class "Default")
      (node (ref "U1") (pin "22") (pinfunction "PA24_22") (pintype "bidirectional"))
    )
    (net (code "63") (name "unconnected-(U3-~{INT}-Pad5)") (class "Default")
      (node (ref "U3") (pin "5") (pinfunction "~{INT}_5") (pintype "bidirectional"))
    )
    (net (code "64") (name "unconnected-(U5-*PG-Pad6)") (class "Default")
      (node (ref "U5") (pin "6") (pinfunction "*PG_6") (pintype "output"))
    )
    (net (code "65") (name "unconnected-(U5-STAT1{slash}*LBO-Pad8)") (class "Default")
      (node (ref "U5") (pin "8") (pinfunction "STAT1/*LBO_8") (pintype "output"))
    )
    (net (code "66") (name "unconnected-(U5-STAT2-Pad7)") (class "Default")
      (node (ref "U5") (pin "7") (pinfunction "STAT2_7") (pintype "output"))
    )
    (net (code "67") (name "unconnected-(U9-PadFB)") (class "Default")
      (node (ref "U9") (pin "FB") (pinfunction "FB_FB") (pintype "bidirectional"))
    )
    (net (code "68") (name "unconnected-(U10-IO0-PadP$4)") (class "Default")
      (node (ref "U10") (pin "P$4") (pinfunction "IO0_P$4") (pintype "bidirectional"))
    )
    (net (code "69") (name "unconnected-(U10-IO7-PadP$12)") (class "Default")
      (node (ref "U10") (pin "P$12") (pinfunction "IO7_P$12") (pintype "bidirectional"))
    )
  )
)
